# Schemeatic_1_0.net
KiCad netlist of a schematic drawn in Altium Designer
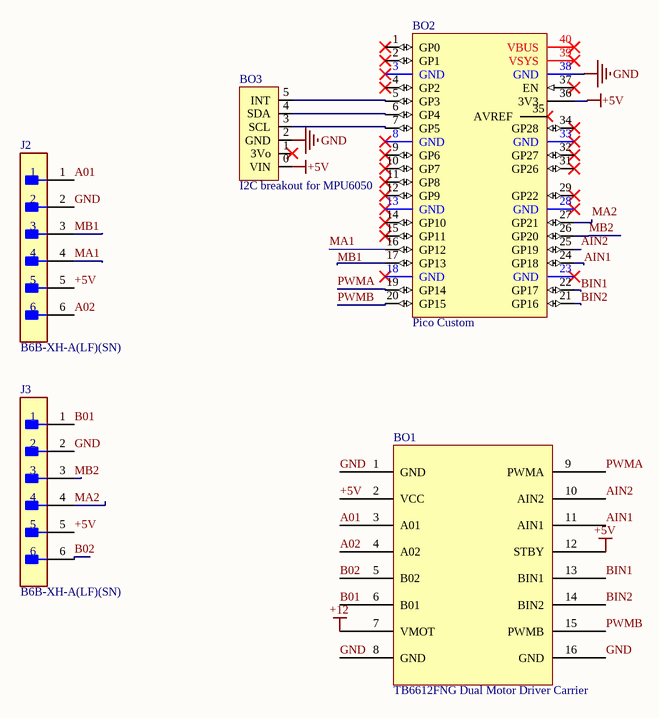
[diagram p0: Schemeatic_1_0.SchDoc]

(export (version "E")
  (design (tool "Eeschema 10.0.6"))
  (components
    (comp (ref "BO1")
      (value "TB6612FNG Dual Motor Driver Carrier")
      (footprint "DIP16 - duplicate1")
      (libsource (lib "motor_16_driver") (part "TB6612FNG_Breakout"))
    )
    (comp (ref "BO2")
      (value "Pico Custom")
      (footprint "DIP40")
      (libsource (lib "pico_lib_custom") (part "PIco_custom_BO"))
    )
    (comp (ref "BO3")
      (value "I2C breakout for MPU6050")
      (footprint "PCBComponent_1")
      (libsource (lib "Integrated_Library1") (part "MPU_6050_IMU_I2C"))
    )
    (comp (ref "J2")
      (value "B6B-XH-A(LF)(SN)")
      (footprint "FP-B6B-XH-A_LF_SN-MFG")
      (description "CONN HEADER VERT 6POS 2.5MM")
      (libsource (lib "Altium Content Vault") (part "f2cb566baf1c37ab5a3b8e90bbeafd6"))
    )
    (comp (ref "J3")
      (value "B6B-XH-A(LF)(SN)")
      (footprint "FP-B6B-XH-A_LF_SN-MFG")
      (description "CONN HEADER VERT 6POS 2.5MM")
      (libsource (lib "Altium Content Vault") (part "f2cb566baf1c37ab5a3b8e90bbeafd6"))
    )
  )
  (nets
    (net (code "1") (name "+5V") (class "Default")
      (node (ref "BO1") (pin "12") (pinfunction "STBY_12") (pintype "passive"))
      (node (ref "BO1") (pin "2") (pinfunction "VCC_2") (pintype "passive"))
      (node (ref "BO2") (pin "36") (pinfunction "3V3_36") (pintype "power_in"))
      (node (ref "BO3") (pin "0") (pinfunction "VIN_0") (pintype "passive"))
      (node (ref "J2") (pin "5") (pinfunction "5_5") (pintype "passive"))
      (node (ref "J3") (pin "5") (pinfunction "5_5") (pintype "passive"))
    )
    (net (code "2") (name "+12") (class "Default")
      (node (ref "BO1") (pin "7") (pinfunction "VMOT_7") (pintype "passive"))
    )
    (net (code "3") (name "/A01") (class "Default")
      (node (ref "BO1") (pin "3") (pinfunction "A01_3") (pintype "passive"))
      (node (ref "J2") (pin "1") (pinfunction "1_1") (pintype "passive"))
    )
    (net (code "4") (name "/A02") (class "Default")
      (node (ref "BO1") (pin "4") (pinfunction "A02_4") (pintype "passive"))
      (node (ref "J2") (pin "6") (pinfunction "6_6") (pintype "passive"))
    )
    (net (code "5") (name "/AIN1") (class "Default")
      (node (ref "BO1") (pin "11") (pinfunction "AIN1_11") (pintype "passive"))
      (node (ref "BO2") (pin "24") (pinfunction "GP18_24") (pintype "bidirectional"))
    )
    (net (code "6") (name "/AIN2") (class "Default")
      (node (ref "BO1") (pin "10") (pinfunction "AIN2_10") (pintype "passive"))
      (node (ref "BO2") (pin "25") (pinfunction "GP19_25") (pintype "bidirectional"))
    )
    (net (code "7") (name "/B01") (class "Default")
      (node (ref "BO1") (pin "6") (pinfunction "B01_6") (pintype "passive"))
      (node (ref "J3") (pin "1") (pinfunction "1_1") (pintype "passive"))
    )
    (net (code "8") (name "/B02") (class "Default")
      (node (ref "BO1") (pin "5") (pinfunction "B02_5") (pintype "passive"))
      (node (ref "J3") (pin "6") (pinfunction "6_6") (pintype "passive"))
    )
    (net (code "9") (name "/BIN1") (class "Default")
      (node (ref "BO1") (pin "13") (pinfunction "BIN1_13") (pintype "passive"))
      (node (ref "BO2") (pin "22") (pinfunction "GP17_22") (pintype "bidirectional"))
    )
    (net (code "10") (name "/BIN2") (class "Default")
      (node (ref "BO1") (pin "14") (pinfunction "BIN2_14") (pintype "passive"))
      (node (ref "BO2") (pin "21") (pinfunction "GP16_21") (pintype "bidirectional"))
    )
    (net (code "11") (name "/MA1") (class "Default")
      (node (ref "BO2") (pin "16") (pinfunction "GP12_16") (pintype "bidirectional"))
      (node (ref "J2") (pin "4") (pinfunction "4_4") (pintype "passive"))
    )
    (net (code "12") (name "/MA2") (class "Default")
      (node (ref "BO2") (pin "27") (pinfunction "GP21_27") (pintype "bidirectional"))
      (node (ref "J3") (pin "4") (pinfunction "4_4") (pintype "passive"))
    )
    (net (code "13") (name "/MB1") (class "Default")
      (node (ref "BO2") (pin "17") (pinfunction "GP13_17") (pintype "bidirectional"))
      (node (ref "J2") (pin "3") (pinfunction "3_3") (pintype "passive"))
    )
    (net (code "14") (name "/MB2") (class "Default")
      (node (ref "BO2") (pin "26") (pinfunction "GP20_26") (pintype "bidirectional"))
      (node (ref "J3") (pin "3") (pinfunction "3_3") (pintype "passive"))
    )
    (net (code "15") (name "/PWMA") (class "Default")
      (node (ref "BO1") (pin "9") (pinfunction "PWMA_9") (pintype "passive"))
      (node (ref "BO2") (pin "19") (pinfunction "GP14_19") (pintype "bidirectional"))
    )
    (net (code "16") (name "/PWMB") (class "Default")
      (node (ref "BO1") (pin "15") (pinfunction "PWMB_15") (pintype "passive"))
      (node (ref "BO2") (pin "20") (pinfunction "GP15_20") (pintype "bidirectional"))
    )
    (net (code "17") (name "GND") (class "Default")
      (node (ref "BO1") (pin "1") (pinfunction "GND_1") (pintype "passive"))
      (node (ref "BO1") (pin "16") (pinfunction "GND_16") (pintype "passive"))
      (node (ref "BO1") (pin "8") (pinfunction "GND_8") (pintype "passive"))
      (node (ref "BO2") (pin "38") (pinfunction "GND_38") (pintype "power_in"))
      (node (ref "BO3") (pin "2") (pinfunction "GND_2") (pintype "passive"))
      (node (ref "J2") (pin "2") (pinfunction "2_2") (pintype "passive"))
      (node (ref "J3") (pin "2") (pinfunction "2_2") (pintype "passive"))
    )
    (net (code "18") (name "Net-(BO2-GP3)") (class "Default")
      (node (ref "BO2") (pin "5") (pinfunction "GP3_5") (pintype "bidirectional"))
      (node (ref "BO3") (pin "5") (pinfunction "INT_5") (pintype "passive"))
    )
    (net (code "19") (name "Net-(BO2-GP4)") (class "Default")
      (node (ref "BO2") (pin "6") (pinfunction "GP4_6") (pintype "bidirectional"))
      (node (ref "BO3") (pin "4") (pinfunction "SDA_4") (pintype "passive"))
    )
    (net (code "20") (name "Net-(BO2-GP5)") (class "Default")
      (node (ref "BO2") (pin "7") (pinfunction "GP5_7") (pintype "bidirectional"))
      (node (ref "BO3") (pin "3") (pinfunction "SCL_3") (pintype "passive"))
    )
    (net (code "21") (name "unconnected-(BO2-AVREF-Pad35)") (class "Default")
      (node (ref "BO2") (pin "35") (pinfunction "AVREF_35") (pintype "power_in+no_connect"))
    )
    (net (code "22") (name "unconnected-(BO2-EN-Pad37)") (class "Default")
      (node (ref "BO2") (pin "37") (pinfunction "EN_37") (pintype "input+no_connect"))
    )
    (net (code "23") (name "unconnected-(BO2-GND-Pad3)") (class "Default")
      (node (ref "BO2") (pin "3") (pinfunction "GND_3") (pintype "power_in+no_connect"))
    )
    (net (code "24") (name "unconnected-(BO2-GND-Pad8)") (class "Default")
      (node (ref "BO2") (pin "8") (pinfunction "GND_8") (pintype "power_in+no_connect"))
    )
    (net (code "25") (name "unconnected-(BO2-GND-Pad13)") (class "Default")
      (node (ref "BO2") (pin "13") (pinfunction "GND_13") (pintype "power_in+no_connect"))
    )
    (net (code "26") (name "unconnected-(BO2-GND-Pad18)") (class "Default")
      (node (ref "BO2") (pin "18") (pinfunction "GND_18") (pintype "power_in+no_connect"))
    )
    (net (code "27") (name "unconnected-(BO2-GND-Pad23)") (class "Default")
      (node (ref "BO2") (pin "23") (pinfunction "GND_23") (pintype "power_in+no_connect"))
    )
    (net (code "28") (name "unconnected-(BO2-GND-Pad28)") (class "Default")
      (node (ref "BO2") (pin "28") (pinfunction "GND_28") (pintype "power_in+no_connect"))
    )
    (net (code "29") (name "unconnected-(BO2-GND-Pad33)") (class "Default")
      (node (ref "BO2") (pin "33") (pinfunction "GND_33") (pintype "power_in+no_connect"))
    )
    (net (code "30") (name "unconnected-(BO2-GP0-Pad1)") (class "Default")
      (node (ref "BO2") (pin "1") (pinfunction "GP0_1") (pintype "bidirectional+no_connect"))
    )
    (net (code "31") (name "unconnected-(BO2-GP1-Pad2)") (class "Default")
      (node (ref "BO2") (pin "2") (pinfunction "GP1_2") (pintype "bidirectional+no_connect"))
    )
    (net (code "32") (name "unconnected-(BO2-GP2-Pad4)") (class "Default")
      (node (ref "BO2") (pin "4") (pinfunction "GP2_4") (pintype "bidirectional+no_connect"))
    )
    (net (code "33") (name "unconnected-(BO2-GP6-Pad9)") (class "Default")
      (node (ref "BO2") (pin "9") (pinfunction "GP6_9") (pintype "bidirectional+no_connect"))
    )
    (net (code "34") (name "unconnected-(BO2-GP7-Pad10)") (class "Default")
      (node (ref "BO2") (pin "10") (pinfunction "GP7_10") (pintype "bidirectional+no_connect"))
    )
    (net (code "35") (name "unconnected-(BO2-GP8-Pad11)") (class "Default")
      (node (ref "BO2") (pin "11") (pinfunction "GP8_11") (pintype "bidirectional+no_connect"))
    )
    (net (code "36") (name "unconnected-(BO2-GP9-Pad12)") (class "Default")
      (node (ref "BO2") (pin "12") (pinfunction "GP9_12") (pintype "bidirectional+no_connect"))
    )
    (net (code "37") (name "unconnected-(BO2-GP10-Pad14)") (class "Default")
      (node (ref "BO2") (pin "14") (pinfunction "GP10_14") (pintype "bidirectional+no_connect"))
    )
    (net (code "38") (name "unconnected-(BO2-GP11-Pad15)") (class "Default")
      (node (ref "BO2") (pin "15") (pinfunction "GP11_15") (pintype "bidirectional+no_connect"))
    )
    (net (code "39") (name "unconnected-(BO2-GP22-Pad29)") (class "Default")
      (node (ref "BO2") (pin "29") (pinfunction "GP22_29") (pintype "bidirectional+no_connect"))
    )
    (net (code "40") (name "unconnected-(BO2-GP26-Pad31)") (class "Default")
      (node (ref "BO2") (pin "31") (pinfunction "GP26_31") (pintype "bidirectional+no_connect"))
    )
    (net (code "41") (name "unconnected-(BO2-GP27-Pad32)") (class "Default")
      (node (ref "BO2") (pin "32") (pinfunction "GP27_32") (pintype "bidirectional+no_connect"))
    )
    (net (code "42") (name "unconnected-(BO2-GP28-Pad34)") (class "Default")
      (node (ref "BO2") (pin "34") (pinfunction "GP28_34") (pintype "bidirectional+no_connect"))
    )
    (net (code "43") (name "unconnected-(BO2-VBUS-Pad40)") (class "Default")
      (node (ref "BO2") (pin "40") (pinfunction "VBUS_40") (pintype "power_in+no_connect"))
    )
    (net (code "44") (name "unconnected-(BO2-VSYS-Pad39)") (class "Default")
      (node (ref "BO2") (pin "39") (pinfunction "VSYS_39") (pintype "power_in+no_connect"))
    )
    (net (code "45") (name "unconnected-(BO3-3Vo-Pad1)") (class "Default")
      (node (ref "BO3") (pin "1") (pinfunction "3Vo_1") (pintype "passive+no_connect"))
    )
  )
)
